# BinaryClock-v5.net
KiCad netlist of a schematic drawn in EAGLE
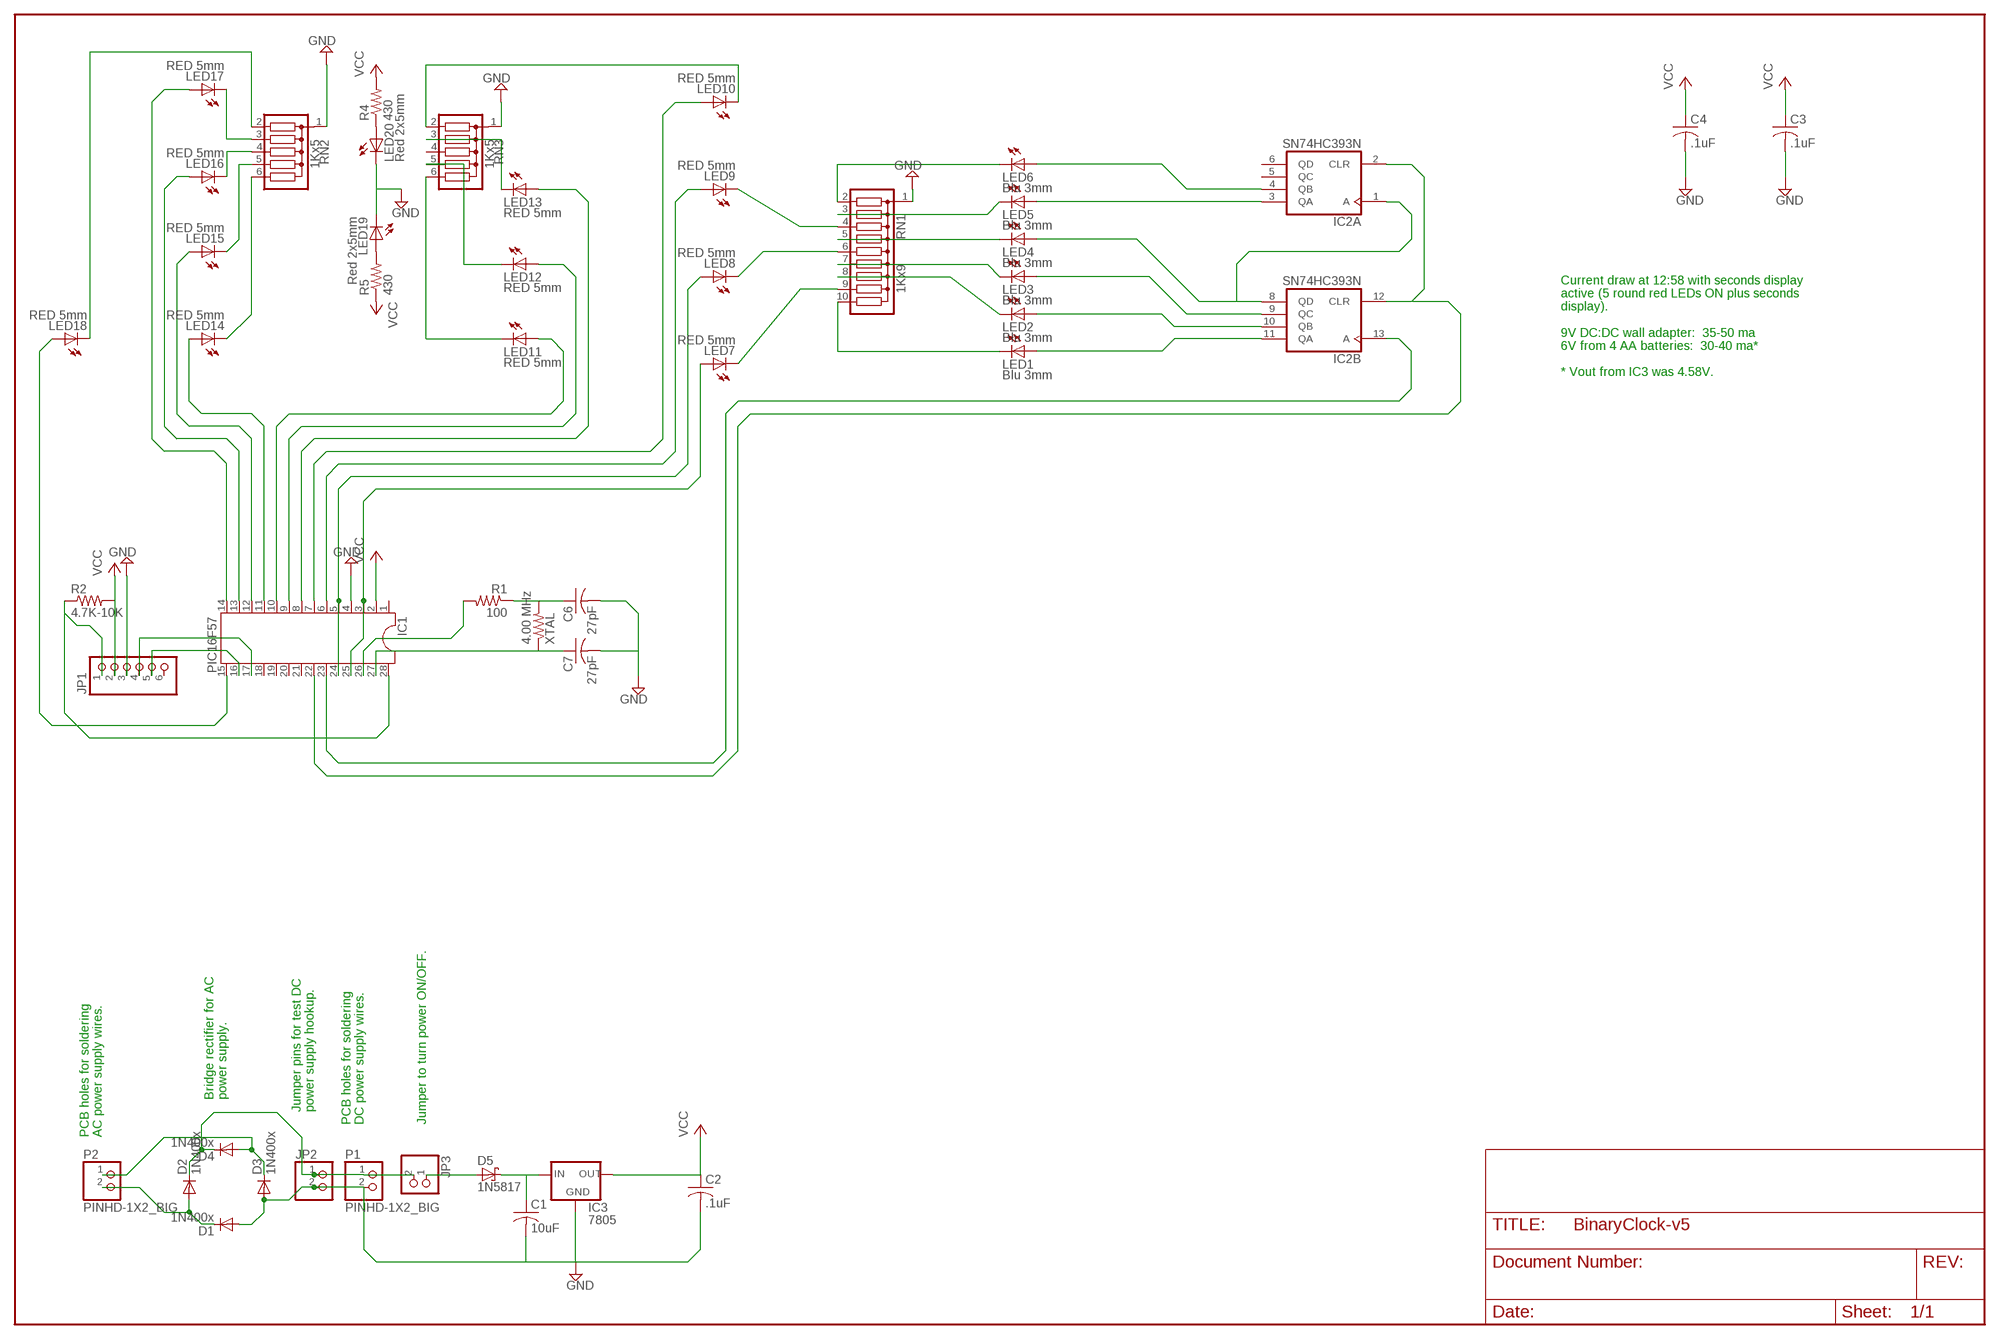
[diagram p0: schematic, sheet 1]

(export (version "E")
  (design (tool "Eeschema 10.0.6"))
  (components
    (comp (ref "C1")
      (value "10uF")
      (footprint "eagle-import:C025-050X050")
      (libsource (lib "eagle-import") (part "C-US025-050X050"))
    )
    (comp (ref "C2")
      (value ".1uF")
      (footprint "eagle-import:C050-025X075")
      (libsource (lib "eagle-import") (part "C-US050-025X075"))
    )
    (comp (ref "C3")
      (value ".1uF")
      (footprint "eagle-import:C050-025X075")
      (libsource (lib "eagle-import") (part "C-US050-025X075"))
    )
    (comp (ref "C4")
      (value ".1uF")
      (footprint "eagle-import:C050-025X075")
      (libsource (lib "eagle-import") (part "C-US050-025X075"))
    )
    (comp (ref "C6")
      (value "27pF")
      (footprint "eagle-import:C025-025X050")
      (libsource (lib "eagle-import") (part "C-US025-025X050"))
    )
    (comp (ref "C7")
      (value "27pF")
      (footprint "eagle-import:C025-025X050")
      (libsource (lib "eagle-import") (part "C-US025-025X050"))
    )
    (comp (ref "D1")
      (value "1N400x")
      (footprint "eagle-import:D-7.5")
      (libsource (lib "eagle-import") (part "DIODE-D-7.5"))
    )
    (comp (ref "D2")
      (value "1N400x")
      (footprint "eagle-import:D-7.5")
      (libsource (lib "eagle-import") (part "DIODE-D-7.5"))
    )
    (comp (ref "D3")
      (value "1N400x")
      (footprint "eagle-import:D-7.5")
      (libsource (lib "eagle-import") (part "DIODE-D-7.5"))
    )
    (comp (ref "D4")
      (value "1N400x")
      (footprint "eagle-import:D-7.5")
      (libsource (lib "eagle-import") (part "DIODE-D-7.5"))
    )
    (comp (ref "D5")
      (value "1N5817")
      (footprint "eagle-import:0207_2V")
      (libsource (lib "eagle-import") (part "1N5817"))
    )
    (comp (ref "IC1")
      (value "PIC16F57")
      (footprint "eagle-import:DIL28-3")
      (libsource (lib "eagle-import") (part "DIL28-3"))
    )
    (comp (ref "IC2")
      (value "SN74HC393N")
      (footprint "eagle-import:DIL14")
      (libsource (lib "eagle-import") (part "74393NHC"))
    )
    (comp (ref "IC3")
      (value "7805")
      (footprint "eagle-import:78MXXS")
      (libsource (lib "eagle-import") (part "78MXXS"))
    )
    (comp (ref "JP1")
      (value "PINHD-1X6/90")
      (footprint "eagle-import:1X06_90")
      (libsource (lib "eagle-import") (part "PINHD-1X6/90"))
    )
    (comp (ref "JP2")
      (value "PINHD-1X2")
      (footprint "eagle-import:1X02")
      (libsource (lib "eagle-import") (part "PINHD-1X2"))
    )
    (comp (ref "JP3")
      (value "PINHD-1X2")
      (footprint "eagle-import:1X02")
      (libsource (lib "eagle-import") (part "PINHD-1X2"))
    )
    (comp (ref "LED1")
      (value "Blu 3mm")
      (footprint "eagle-import:LED3MM")
      (libsource (lib "eagle-import") (part "LED3MM"))
    )
    (comp (ref "LED2")
      (value "Blu 3mm")
      (footprint "eagle-import:LED3MM")
      (libsource (lib "eagle-import") (part "LED3MM"))
    )
    (comp (ref "LED3")
      (value "Blu 3mm")
      (footprint "eagle-import:LED3MM")
      (libsource (lib "eagle-import") (part "LED3MM"))
    )
    (comp (ref "LED4")
      (value "Blu 3mm")
      (footprint "eagle-import:LED3MM")
      (libsource (lib "eagle-import") (part "LED3MM"))
    )
    (comp (ref "LED5")
      (value "Blu 3mm")
      (footprint "eagle-import:LED3MM")
      (libsource (lib "eagle-import") (part "LED3MM"))
    )
    (comp (ref "LED6")
      (value "Blu 3mm")
      (footprint "eagle-import:LED3MM")
      (libsource (lib "eagle-import") (part "LED3MM"))
    )
    (comp (ref "LED7")
      (value "RED 5mm")
      (footprint "eagle-import:LED5MM")
      (libsource (lib "eagle-import") (part "LED5MM"))
    )
    (comp (ref "LED8")
      (value "RED 5mm")
      (footprint "eagle-import:LED5MM")
      (libsource (lib "eagle-import") (part "LED5MM"))
    )
    (comp (ref "LED9")
      (value "RED 5mm")
      (footprint "eagle-import:LED5MM")
      (libsource (lib "eagle-import") (part "LED5MM"))
    )
    (comp (ref "LED10")
      (value "RED 5mm")
      (footprint "eagle-import:LED5MM")
      (libsource (lib "eagle-import") (part "LED5MM"))
    )
    (comp (ref "LED11")
      (value "RED 5mm")
      (footprint "eagle-import:LED5MM")
      (libsource (lib "eagle-import") (part "LED5MM"))
    )
    (comp (ref "LED12")
      (value "RED 5mm")
      (footprint "eagle-import:LED5MM")
      (libsource (lib "eagle-import") (part "LED5MM"))
    )
    (comp (ref "LED13")
      (value "RED 5mm")
      (footprint "eagle-import:LED5MM")
      (libsource (lib "eagle-import") (part "LED5MM"))
    )
    (comp (ref "LED14")
      (value "RED 5mm")
      (footprint "eagle-import:LED5MM")
      (libsource (lib "eagle-import") (part "LED5MM"))
    )
    (comp (ref "LED15")
      (value "RED 5mm")
      (footprint "eagle-import:LED5MM")
      (libsource (lib "eagle-import") (part "LED5MM"))
    )
    (comp (ref "LED16")
      (value "RED 5mm")
      (footprint "eagle-import:LED5MM")
      (libsource (lib "eagle-import") (part "LED5MM"))
    )
    (comp (ref "LED17")
      (value "RED 5mm")
      (footprint "eagle-import:LED5MM")
      (libsource (lib "eagle-import") (part "LED5MM"))
    )
    (comp (ref "LED18")
      (value "RED 5mm")
      (footprint "eagle-import:LED5MM")
      (libsource (lib "eagle-import") (part "LED5MM"))
    )
    (comp (ref "LED19")
      (value "Red 2x5mm")
      (footprint "eagle-import:U57X32")
      (libsource (lib "eagle-import") (part "U57X32"))
    )
    (comp (ref "LED20")
      (value "Red 2x5mm")
      (footprint "eagle-import:U57X32")
      (libsource (lib "eagle-import") (part "U57X32"))
    )
    (comp (ref "P1")
      (value "PINHD-1X2_BIG")
      (footprint "eagle-import:1X02_BIG")
      (libsource (lib "eagle-import") (part "PINHD-1X2_BIG"))
    )
    (comp (ref "P2")
      (value "PINHD-1X2_BIG")
      (footprint "eagle-import:1X02_BIG")
      (libsource (lib "eagle-import") (part "PINHD-1X2_BIG"))
    )
    (comp (ref "R1")
      (value "100")
      (footprint "eagle-import:0207_7")
      (libsource (lib "eagle-import") (part "R-US_0207/7"))
    )
    (comp (ref "R2")
      (value "4.7K-10K")
      (footprint "eagle-import:0207_2V")
      (libsource (lib "eagle-import") (part "R-US_0207/2V"))
    )
    (comp (ref "R4")
      (value "430")
      (footprint "eagle-import:0204_5")
      (libsource (lib "eagle-import") (part "R-US_0204/5"))
    )
    (comp (ref "R5")
      (value "430")
      (footprint "eagle-import:0204_7")
      (libsource (lib "eagle-import") (part "R-US_0204/7"))
    )
    (comp (ref "RN1")
      (value "1Kx9")
      (footprint "eagle-import:SIL10")
      (libsource (lib "eagle-import") (part "G09R"))
    )
    (comp (ref "RN2")
      (value "1Kx5")
      (footprint "eagle-import:SIL6")
      (libsource (lib "eagle-import") (part "G05R"))
    )
    (comp (ref "RN3")
      (value "1Kx5")
      (footprint "eagle-import:SIL6")
      (libsource (lib "eagle-import") (part "G05R"))
    )
    (comp (ref "XTAL")
      (value "4.00 MHz")
      (footprint "eagle-import:0204_5")
      (libsource (lib "eagle-import") (part "R-US_0204/5"))
    )
  )
  (nets
    (net (code "1") (name "GND") (class "Default")
      (node (ref "C1") (pin "2") (pinfunction "2_2") (pintype "passive"))
      (node (ref "C2") (pin "2") (pinfunction "2_2") (pintype "passive"))
      (node (ref "C3") (pin "2") (pinfunction "2_2") (pintype "passive"))
      (node (ref "C4") (pin "2") (pinfunction "2_2") (pintype "passive"))
      (node (ref "C6") (pin "2") (pinfunction "2_2") (pintype "passive"))
      (node (ref "C7") (pin "2") (pinfunction "2_2") (pintype "passive"))
      (node (ref "D1") (pin "A") (pinfunction "A_A") (pintype "passive"))
      (node (ref "D3") (pin "A") (pinfunction "A_A") (pintype "passive"))
      (node (ref "IC1") (pin "4") (pinfunction "4_4") (pintype "passive"))
      (node (ref "IC3") (pin "GND") (pinfunction "GND_GND") (pintype "input"))
      (node (ref "JP1") (pin "3") (pinfunction "3_3") (pintype "passive"))
      (node (ref "JP2") (pin "2") (pinfunction "2_2") (pintype "passive"))
      (node (ref "LED19") (pin "K") (pinfunction "C_K") (pintype "passive"))
      (node (ref "LED20") (pin "K") (pinfunction "C_K") (pintype "passive"))
      (node (ref "P1") (pin "2") (pinfunction "2_2") (pintype "passive"))
      (node (ref "RN1") (pin "1") (pinfunction "1_1") (pintype "passive"))
      (node (ref "RN2") (pin "1") (pinfunction "1_1") (pintype "passive"))
      (node (ref "RN3") (pin "1") (pinfunction "1_1") (pintype "passive"))
    )
    (net (code "2") (name "Net-(C6-Pad1)") (class "Default")
      (node (ref "C6") (pin "1") (pinfunction "1_1") (pintype "passive"))
      (node (ref "R1") (pin "1") (pinfunction "1_1") (pintype "passive"))
      (node (ref "XTAL") (pin "2") (pinfunction "2_2") (pintype "passive"))
    )
    (net (code "3") (name "Net-(C7-Pad1)") (class "Default")
      (node (ref "C7") (pin "1") (pinfunction "1_1") (pintype "passive"))
      (node (ref "IC1") (pin "27") (pinfunction "27_27") (pintype "passive"))
      (node (ref "XTAL") (pin "1") (pinfunction "1_1") (pintype "passive"))
    )
    (net (code "4") (name "Net-(D1-PadC)") (class "Default")
      (node (ref "D1") (pin "C") (pinfunction "C_C") (pintype "passive"))
      (node (ref "D2") (pin "A") (pinfunction "A_A") (pintype "passive"))
      (node (ref "P2") (pin "2") (pinfunction "2_2") (pintype "passive"))
    )
    (net (code "5") (name "Net-(D2-PadC)") (class "Default")
      (node (ref "D2") (pin "C") (pinfunction "C_C") (pintype "passive"))
      (node (ref "D4") (pin "C") (pinfunction "C_C") (pintype "passive"))
      (node (ref "JP2") (pin "1") (pinfunction "1_1") (pintype "passive"))
      (node (ref "JP3") (pin "2") (pinfunction "2_2") (pintype "passive"))
      (node (ref "P1") (pin "1") (pinfunction "1_1") (pintype "passive"))
    )
    (net (code "6") (name "Net-(D3-PadC)") (class "Default")
      (node (ref "D3") (pin "C") (pinfunction "C_C") (pintype "passive"))
      (node (ref "D4") (pin "A") (pinfunction "A_A") (pintype "passive"))
      (node (ref "P2") (pin "1") (pinfunction "1_1") (pintype "passive"))
    )
    (net (code "7") (name "Net-(D5-A)") (class "Default")
      (node (ref "D5") (pin "1") (pinfunction "A_1") (pintype "passive"))
      (node (ref "JP3") (pin "1") (pinfunction "1_1") (pintype "passive"))
    )
    (net (code "8") (name "Net-(D5-C)") (class "Default")
      (node (ref "C1") (pin "1") (pinfunction "1_1") (pintype "passive"))
      (node (ref "D5") (pin "2") (pinfunction "C_2") (pintype "passive"))
      (node (ref "IC3") (pin "IN") (pinfunction "IN_IN") (pintype "input"))
    )
    (net (code "9") (name "Net-(IC1-Pad6)") (class "Default")
      (node (ref "IC1") (pin "6") (pinfunction "6_6") (pintype "passive"))
      (node (ref "LED9") (pin "A") (pinfunction "A_A") (pintype "passive"))
    )
    (net (code "10") (name "Net-(IC1-Pad7)") (class "Default")
      (node (ref "IC1") (pin "7") (pinfunction "7_7") (pintype "passive"))
      (node (ref "LED10") (pin "A") (pinfunction "A_A") (pintype "passive"))
    )
    (net (code "11") (name "Net-(IC1-Pad8)") (class "Default")
      (node (ref "IC1") (pin "8") (pinfunction "8_8") (pintype "passive"))
      (node (ref "LED13") (pin "A") (pinfunction "A_A") (pintype "passive"))
    )
    (net (code "12") (name "Net-(IC1-Pad9)") (class "Default")
      (node (ref "IC1") (pin "9") (pinfunction "9_9") (pintype "passive"))
      (node (ref "LED12") (pin "A") (pinfunction "A_A") (pintype "passive"))
    )
    (net (code "13") (name "Net-(IC1-Pad10)") (class "Default")
      (node (ref "IC1") (pin "10") (pinfunction "10_10") (pintype "passive"))
      (node (ref "LED11") (pin "A") (pinfunction "A_A") (pintype "passive"))
    )
    (net (code "14") (name "Net-(IC1-Pad11)") (class "Default")
      (node (ref "IC1") (pin "11") (pinfunction "11_11") (pintype "passive"))
      (node (ref "LED14") (pin "A") (pinfunction "A_A") (pintype "passive"))
    )
    (net (code "15") (name "Net-(IC1-Pad12)") (class "Default")
      (node (ref "IC1") (pin "12") (pinfunction "12_12") (pintype "passive"))
      (node (ref "LED15") (pin "A") (pinfunction "A_A") (pintype "passive"))
    )
    (net (code "16") (name "Net-(IC1-Pad13)") (class "Default")
      (node (ref "IC1") (pin "13") (pinfunction "13_13") (pintype "passive"))
      (node (ref "LED16") (pin "A") (pinfunction "A_A") (pintype "passive"))
    )
    (net (code "17") (name "Net-(IC1-Pad14)") (class "Default")
      (node (ref "IC1") (pin "14") (pinfunction "14_14") (pintype "passive"))
      (node (ref "LED17") (pin "A") (pinfunction "A_A") (pintype "passive"))
    )
    (net (code "18") (name "Net-(IC1-Pad15)") (class "Default")
      (node (ref "IC1") (pin "15") (pinfunction "15_15") (pintype "passive"))
      (node (ref "LED18") (pin "A") (pinfunction "A_A") (pintype "passive"))
    )
    (net (code "19") (name "Net-(IC1-Pad16)") (class "Default")
      (node (ref "IC1") (pin "16") (pinfunction "16_16") (pintype "passive"))
      (node (ref "JP1") (pin "5") (pinfunction "5_5") (pintype "passive"))
    )
    (net (code "20") (name "Net-(IC1-Pad17)") (class "Default")
      (node (ref "IC1") (pin "17") (pinfunction "17_17") (pintype "passive"))
      (node (ref "JP1") (pin "4") (pinfunction "4_4") (pintype "passive"))
    )
    (net (code "21") (name "Net-(IC1-Pad24)") (class "Default")
      (node (ref "IC1") (pin "24") (pinfunction "24_24") (pintype "passive"))
      (node (ref "IC1") (pin "5") (pinfunction "5_5") (pintype "passive"))
      (node (ref "LED8") (pin "A") (pinfunction "A_A") (pintype "passive"))
    )
    (net (code "22") (name "Net-(IC1-Pad25)") (class "Default")
      (node (ref "IC1") (pin "25") (pinfunction "25_25") (pintype "passive"))
      (node (ref "IC1") (pin "3") (pinfunction "3_3") (pintype "passive"))
      (node (ref "LED7") (pin "A") (pinfunction "A_A") (pintype "passive"))
    )
    (net (code "23") (name "Net-(IC1-Pad26)") (class "Default")
      (node (ref "IC1") (pin "26") (pinfunction "26_26") (pintype "passive"))
      (node (ref "R1") (pin "2") (pinfunction "2_2") (pintype "passive"))
    )
    (net (code "24") (name "Net-(IC1-Pad28)") (class "Default")
      (node (ref "IC1") (pin "28") (pinfunction "28_28") (pintype "passive"))
      (node (ref "JP1") (pin "1") (pinfunction "1_1") (pintype "passive"))
      (node (ref "R2") (pin "1") (pinfunction "1_1") (pintype "passive"))
    )
    (net (code "25") (name "Net-(IC2A-A)") (class "Default")
      (node (ref "IC2") (pin "1") (pinfunction "A_1") (pintype "input"))
      (node (ref "IC2") (pin "8") (pinfunction "QD_8") (pintype "output"))
      (node (ref "LED4") (pin "A") (pinfunction "A_A") (pintype "passive"))
    )
    (net (code "26") (name "Net-(IC2A-CLR)") (class "Default")
      (node (ref "IC1") (pin "22") (pinfunction "22_22") (pintype "passive"))
      (node (ref "IC2") (pin "12") (pinfunction "CLR_12") (pintype "input"))
      (node (ref "IC2") (pin "2") (pinfunction "CLR_2") (pintype "input"))
    )
    (net (code "27") (name "Net-(IC2A-QA)") (class "Default")
      (node (ref "IC2") (pin "3") (pinfunction "QA_3") (pintype "output"))
      (node (ref "LED5") (pin "A") (pinfunction "A_A") (pintype "passive"))
    )
    (net (code "28") (name "Net-(IC2A-QB)") (class "Default")
      (node (ref "IC2") (pin "4") (pinfunction "QB_4") (pintype "output"))
      (node (ref "LED6") (pin "A") (pinfunction "A_A") (pintype "passive"))
    )
    (net (code "29") (name "Net-(IC2B-A)") (class "Default")
      (node (ref "IC1") (pin "23") (pinfunction "23_23") (pintype "passive"))
      (node (ref "IC2") (pin "13") (pinfunction "A_13") (pintype "input"))
    )
    (net (code "30") (name "Net-(IC2B-QA)") (class "Default")
      (node (ref "IC2") (pin "11") (pinfunction "QA_11") (pintype "output"))
      (node (ref "LED1") (pin "A") (pinfunction "A_A") (pintype "passive"))
    )
    (net (code "31") (name "Net-(IC2B-QB)") (class "Default")
      (node (ref "IC2") (pin "10") (pinfunction "QB_10") (pintype "output"))
      (node (ref "LED2") (pin "A") (pinfunction "A_A") (pintype "passive"))
    )
    (net (code "32") (name "Net-(IC2B-QC)") (class "Default")
      (node (ref "IC2") (pin "9") (pinfunction "QC_9") (pintype "output"))
      (node (ref "LED3") (pin "A") (pinfunction "A_A") (pintype "passive"))
    )
    (net (code "33") (name "Net-(LED1-C)") (class "Default")
      (node (ref "LED1") (pin "K") (pinfunction "C_K") (pintype "passive"))
      (node (ref "RN1") (pin "10") (pinfunction "10_10") (pintype "passive"))
    )
    (net (code "34") (name "Net-(LED2-C)") (class "Default")
      (node (ref "LED2") (pin "K") (pinfunction "C_K") (pintype "passive"))
      (node (ref "RN1") (pin "8") (pinfunction "8_8") (pintype "passive"))
    )
    (net (code "35") (name "Net-(LED3-C)") (class "Default")
      (node (ref "LED3") (pin "K") (pinfunction "C_K") (pintype "passive"))
      (node (ref "RN1") (pin "7") (pinfunction "7_7") (pintype "passive"))
    )
    (net (code "36") (name "Net-(LED4-C)") (class "Default")
      (node (ref "LED4") (pin "K") (pinfunction "C_K") (pintype "passive"))
      (node (ref "RN1") (pin "5") (pinfunction "5_5") (pintype "passive"))
    )
    (net (code "37") (name "Net-(LED5-C)") (class "Default")
      (node (ref "LED5") (pin "K") (pinfunction "C_K") (pintype "passive"))
      (node (ref "RN1") (pin "3") (pinfunction "3_3") (pintype "passive"))
    )
    (net (code "38") (name "Net-(LED6-C)") (class "Default")
      (node (ref "LED6") (pin "K") (pinfunction "C_K") (pintype "passive"))
      (node (ref "RN1") (pin "2") (pinfunction "2_2") (pintype "passive"))
    )
    (net (code "39") (name "Net-(LED7-C)") (class "Default")
      (node (ref "LED7") (pin "K") (pinfunction "C_K") (pintype "passive"))
      (node (ref "RN1") (pin "9") (pinfunction "9_9") (pintype "passive"))
    )
    (net (code "40") (name "Net-(LED8-C)") (class "Default")
      (node (ref "LED8") (pin "K") (pinfunction "C_K") (pintype "passive"))
      (node (ref "RN1") (pin "6") (pinfunction "6_6") (pintype "passive"))
    )
    (net (code "41") (name "Net-(LED9-C)") (class "Default")
      (node (ref "LED9") (pin "K") (pinfunction "C_K") (pintype "passive"))
      (node (ref "RN1") (pin "4") (pinfunction "4_4") (pintype "passive"))
    )
    (net (code "42") (name "Net-(LED10-C)") (class "Default")
      (node (ref "LED10") (pin "K") (pinfunction "C_K") (pintype "passive"))
      (node (ref "RN3") (pin "2") (pinfunction "2_2") (pintype "passive"))
    )
    (net (code "43") (name "Net-(LED11-C)") (class "Default")
      (node (ref "LED11") (pin "K") (pinfunction "C_K") (pintype "passive"))
      (node (ref "RN3") (pin "6") (pinfunction "6_6") (pintype "passive"))
    )
    (net (code "44") (name "Net-(LED12-C)") (class "Default")
      (node (ref "LED12") (pin "K") (pinfunction "C_K") (pintype "passive"))
      (node (ref "RN3") (pin "5") (pinfunction "5_5") (pintype "passive"))
    )
    (net (code "45") (name "Net-(LED13-C)") (class "Default")
      (node (ref "LED13") (pin "K") (pinfunction "C_K") (pintype "passive"))
      (node (ref "RN3") (pin "3") (pinfunction "3_3") (pintype "passive"))
    )
    (net (code "46") (name "Net-(LED14-C)") (class "Default")
      (node (ref "LED14") (pin "K") (pinfunction "C_K") (pintype "passive"))
      (node (ref "RN2") (pin "6") (pinfunction "6_6") (pintype "passive"))
    )
    (net (code "47") (name "Net-(LED15-C)") (class "Default")
      (node (ref "LED15") (pin "K") (pinfunction "C_K") (pintype "passive"))
      (node (ref "RN2") (pin "5") (pinfunction "5_5") (pintype "passive"))
    )
    (net (code "48") (name "Net-(LED16-C)") (class "Default")
      (node (ref "LED16") (pin "K") (pinfunction "C_K") (pintype "passive"))
      (node (ref "RN2") (pin "4") (pinfunction "4_4") (pintype "passive"))
    )
    (net (code "49") (name "Net-(LED17-C)") (class "Default")
      (node (ref "LED17") (pin "K") (pinfunction "C_K") (pintype "passive"))
      (node (ref "RN2") (pin "3") (pinfunction "3_3") (pintype "passive"))
    )
    (net (code "50") (name "Net-(LED18-C)") (class "Default")
      (node (ref "LED18") (pin "K") (pinfunction "C_K") (pintype "passive"))
      (node (ref "RN2") (pin "2") (pinfunction "2_2") (pintype "passive"))
    )
    (net (code "51") (name "Net-(LED19-PadA)") (class "Default")
      (node (ref "LED19") (pin "A") (pinfunction "A_A") (pintype "passive"))
      (node (ref "R5") (pin "2") (pinfunction "2_2") (pintype "passive"))
    )
    (net (code "52") (name "Net-(LED20-PadA)") (class "Default")
      (node (ref "LED20") (pin "A") (pinfunction "A_A") (pintype "passive"))
      (node (ref "R4") (pin "1") (pinfunction "1_1") (pintype "passive"))
    )
    (net (code "53") (name "VCC") (class "Default")
      (node (ref "C2") (pin "1") (pinfunction "1_1") (pintype "passive"))
      (node (ref "C3") (pin "1") (pinfunction "1_1") (pintype "passive"))
      (node (ref "C4") (pin "1") (pinfunction "1_1") (pintype "passive"))
      (node (ref "IC1") (pin "2") (pinfunction "2_2") (pintype "passive"))
      (node (ref "IC3") (pin "OUT") (pinfunction "OUT_OUT") (pintype "passive"))
      (node (ref "JP1") (pin "2") (pinfunction "2_2") (pintype "passive"))
      (node (ref "R2") (pin "2") (pinfunction "2_2") (pintype "passive"))
      (node (ref "R4") (pin "2") (pinfunction "2_2") (pintype "passive"))
      (node (ref "R5") (pin "1") (pinfunction "1_1") (pintype "passive"))
    )
    (net (code "54") (name "unconnected-(IC1-Pad1)") (class "Default")
      (node (ref "IC1") (pin "1") (pinfunction "1_1") (pintype "passive"))
    )
    (net (code "55") (name "unconnected-(IC1-Pad18)") (class "Default")
      (node (ref "IC1") (pin "18") (pinfunction "18_18") (pintype "passive"))
    )
    (net (code "56") (name "unconnected-(IC1-Pad19)") (class "Default")
      (node (ref "IC1") (pin "19") (pinfunction "19_19") (pintype "passive"))
    )
    (net (code "57") (name "unconnected-(IC1-Pad20)") (class "Default")
      (node (ref "IC1") (pin "20") (pinfunction "20_20") (pintype "passive"))
    )
    (net (code "58") (name "unconnected-(IC1-Pad21)") (class "Default")
      (node (ref "IC1") (pin "21") (pinfunction "21_21") (pintype "passive"))
    )
    (net (code "59") (name "unconnected-(IC2A-QC-Pad5)") (class "Default")
      (node (ref "IC2") (pin "5") (pinfunction "QC_5") (pintype "output"))
    )
    (net (code "60") (name "unconnected-(IC2A-QD-Pad6)") (class "Default")
      (node (ref "IC2") (pin "6") (pinfunction "QD_6") (pintype "output"))
    )
    (net (code "61") (name "unconnected-(JP1-Pad6)") (class "Default")
      (node (ref "JP1") (pin "6") (pinfunction "6_6") (pintype "passive"))
    )
    (net (code "62") (name "unconnected-(RN3-Pad4)") (class "Default")
      (node (ref "RN3") (pin "4") (pinfunction "4_4") (pintype "passive"))
    )
  )
)
